# BikeLight.net
KiCad netlist of a schematic drawn in EAGLE
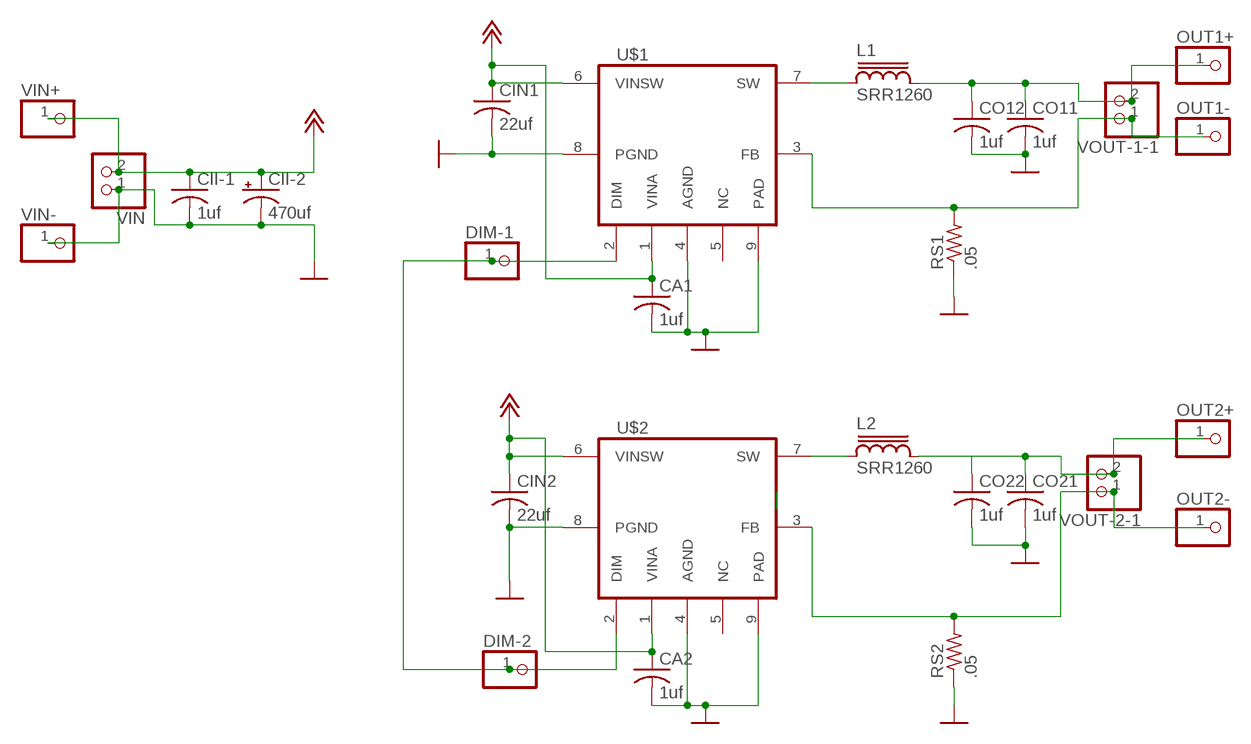
[diagram p0: schematic, sheet 1]

(export (version "E")
  (design (tool "Eeschema 10.0.6"))
  (components
    (comp (ref "CA1")
      (value "1uf")
      (footprint "eagle-import:C1210")
      (libsource (lib "eagle-import") (part "C-USC1210"))
    )
    (comp (ref "CA2")
      (value "1uf")
      (footprint "eagle-import:C1210")
      (libsource (lib "eagle-import") (part "C-USC1210"))
    )
    (comp (ref "CII-1")
      (value "1uf")
      (footprint "eagle-import:C1210")
      (libsource (lib "eagle-import") (part "C-USC1210"))
    )
    (comp (ref "CII-2")
      (value "470uf")
      (footprint "eagle-import:UD-10X10_NICHICON")
      (libsource (lib "eagle-import") (part "CPOL-USUD-10X10"))
    )
    (comp (ref "CIN1")
      (value "22uf")
      (footprint "eagle-import:C1210")
      (libsource (lib "eagle-import") (part "C-USC1210"))
    )
    (comp (ref "CIN2")
      (value "22uf")
      (footprint "eagle-import:C1210")
      (libsource (lib "eagle-import") (part "C-USC1210"))
    )
    (comp (ref "CO11")
      (value "1uf")
      (footprint "eagle-import:C1210")
      (libsource (lib "eagle-import") (part "C-USC1210"))
    )
    (comp (ref "CO12")
      (value "1uf")
      (footprint "eagle-import:C1210")
      (libsource (lib "eagle-import") (part "C-USC1210"))
    )
    (comp (ref "CO21")
      (value "1uf")
      (footprint "eagle-import:C1210")
      (libsource (lib "eagle-import") (part "C-USC1210"))
    )
    (comp (ref "CO22")
      (value "1uf")
      (footprint "eagle-import:C1210")
      (libsource (lib "eagle-import") (part "C-USC1210"))
    )
    (comp (ref "DIM-1")
      (value "PINHD-1X1")
      (footprint "eagle-import:1X01")
      (libsource (lib "eagle-import") (part "PINHD-1X1"))
    )
    (comp (ref "DIM-2")
      (value "PINHD-1X1")
      (footprint "eagle-import:1X01")
      (libsource (lib "eagle-import") (part "PINHD-1X1"))
    )
    (comp (ref "L1")
      (value "SRR1260")
      (footprint "eagle-import:SRR1260")
      (libsource (lib "eagle-import") (part "SRR1260"))
    )
    (comp (ref "L2")
      (value "SRR1260")
      (footprint "eagle-import:SRR1260")
      (libsource (lib "eagle-import") (part "SRR1260"))
    )
    (comp (ref "OUT1+")
      (value "PINHD-1X1")
      (footprint "eagle-import:1X01")
      (libsource (lib "eagle-import") (part "PINHD-1X1"))
    )
    (comp (ref "OUT1-")
      (value "PINHD-1X1")
      (footprint "eagle-import:1X01")
      (libsource (lib "eagle-import") (part "PINHD-1X1"))
    )
    (comp (ref "OUT2+")
      (value "PINHD-1X1")
      (footprint "eagle-import:1X01")
      (libsource (lib "eagle-import") (part "PINHD-1X1"))
    )
    (comp (ref "OUT2-")
      (value "PINHD-1X1")
      (footprint "eagle-import:1X01")
      (libsource (lib "eagle-import") (part "PINHD-1X1"))
    )
    (comp (ref "RS1")
      (value ".05")
      (footprint "eagle-import:R1206")
      (libsource (lib "eagle-import") (part "R-US_R1206"))
    )
    (comp (ref "RS2")
      (value ".05")
      (footprint "eagle-import:R1206")
      (libsource (lib "eagle-import") (part "R-US_R1206"))
    )
    (comp (ref "U$1")
      (value "LED2001PHR")
      (footprint "eagle-import:SOIC127P600X170-9N")
      (libsource (lib "eagle-import") (part "LED2001PHR"))
    )
    (comp (ref "U$2")
      (value "LED2001PHR")
      (footprint "eagle-import:SOIC127P600X170-9N")
      (libsource (lib "eagle-import") (part "LED2001PHR"))
    )
    (comp (ref "VIN")
      (value "PINHD-1X2")
      (footprint "eagle-import:1X02")
      (libsource (lib "eagle-import") (part "PINHD-1X2"))
    )
    (comp (ref "VIN+")
      (value "PINHD-1X1")
      (footprint "eagle-import:1X01")
      (libsource (lib "eagle-import") (part "PINHD-1X1"))
    )
    (comp (ref "VIN-")
      (value "PINHD-1X1")
      (footprint "eagle-import:1X01")
      (libsource (lib "eagle-import") (part "PINHD-1X1"))
    )
    (comp (ref "VOUT-1-1")
      (value "PINHD-1X2")
      (footprint "eagle-import:1X02")
      (libsource (lib "eagle-import") (part "PINHD-1X2"))
    )
    (comp (ref "VOUT-2-1")
      (value "PINHD-1X2")
      (footprint "eagle-import:1X02")
      (libsource (lib "eagle-import") (part "PINHD-1X2"))
    )
  )
  (nets
    (net (code "1") (name "+12V") (class "Default")
      (node (ref "CA1") (pin "1") (pinfunction "1_1") (pintype "passive"))
      (node (ref "CA2") (pin "1") (pinfunction "1_1") (pintype "passive"))
      (node (ref "CII-1") (pin "1") (pinfunction "1_1") (pintype "passive"))
      (node (ref "CII-2") (pin "+") (pinfunction "+_+") (pintype "passive"))
      (node (ref "CIN1") (pin "1") (pinfunction "1_1") (pintype "passive"))
      (node (ref "CIN2") (pin "1") (pinfunction "1_1") (pintype "passive"))
      (node (ref "U$1") (pin "1") (pinfunction "VINA_1") (pintype "input"))
      (node (ref "U$1") (pin "6") (pinfunction "VINSW_6") (pintype "input"))
      (node (ref "U$2") (pin "1") (pinfunction "VINA_1") (pintype "input"))
      (node (ref "U$2") (pin "6") (pinfunction "VINSW_6") (pintype "input"))
      (node (ref "VIN") (pin "2") (pinfunction "2_2") (pintype "passive"))
      (node (ref "VIN+") (pin "1") (pinfunction "1_1") (pintype "passive"))
    )
    (net (code "2") (name "GND") (class "Default")
      (node (ref "CA1") (pin "2") (pinfunction "2_2") (pintype "passive"))
      (node (ref "CA2") (pin "2") (pinfunction "2_2") (pintype "passive"))
      (node (ref "CII-1") (pin "2") (pinfunction "2_2") (pintype "passive"))
      (node (ref "CII-2") (pin "-") (pinfunction "-_-") (pintype "passive"))
      (node (ref "CIN1") (pin "2") (pinfunction "2_2") (pintype "passive"))
      (node (ref "CIN2") (pin "2") (pinfunction "2_2") (pintype "passive"))
      (node (ref "CO11") (pin "2") (pinfunction "2_2") (pintype "passive"))
      (node (ref "CO12") (pin "2") (pinfunction "2_2") (pintype "passive"))
      (node (ref "CO21") (pin "2") (pinfunction "2_2") (pintype "passive"))
      (node (ref "CO22") (pin "2") (pinfunction "2_2") (pintype "passive"))
      (node (ref "RS1") (pin "1") (pinfunction "1_1") (pintype "passive"))
      (node (ref "RS2") (pin "1") (pinfunction "1_1") (pintype "passive"))
      (node (ref "U$1") (pin "4") (pinfunction "AGND_4") (pintype "input"))
      (node (ref "U$1") (pin "8") (pinfunction "PGND_8") (pintype "input"))
      (node (ref "U$1") (pin "9") (pinfunction "PAD_9") (pintype "input"))
      (node (ref "U$2") (pin "4") (pinfunction "AGND_4") (pintype "input"))
      (node (ref "U$2") (pin "8") (pinfunction "PGND_8") (pintype "input"))
      (node (ref "U$2") (pin "9") (pinfunction "PAD_9") (pintype "input"))
      (node (ref "VIN") (pin "1") (pinfunction "1_1") (pintype "passive"))
      (node (ref "VIN-") (pin "1") (pinfunction "1_1") (pintype "passive"))
    )
    (net (code "3") (name "Net-(CO11-Pad1)") (class "Default")
      (node (ref "CO11") (pin "1") (pinfunction "1_1") (pintype "passive"))
      (node (ref "CO12") (pin "1") (pinfunction "1_1") (pintype "passive"))
      (node (ref "L1") (pin "2") (pinfunction "2_2") (pintype "passive"))
      (node (ref "OUT1+") (pin "1") (pinfunction "1_1") (pintype "passive"))
      (node (ref "VOUT-1-1") (pin "2") (pinfunction "2_2") (pintype "passive"))
    )
    (net (code "4") (name "Net-(CO21-Pad1)") (class "Default")
      (node (ref "CO21") (pin "1") (pinfunction "1_1") (pintype "passive"))
      (node (ref "CO22") (pin "1") (pinfunction "1_1") (pintype "passive"))
      (node (ref "L2") (pin "2") (pinfunction "2_2") (pintype "passive"))
      (node (ref "OUT2+") (pin "1") (pinfunction "1_1") (pintype "passive"))
      (node (ref "VOUT-2-1") (pin "2") (pinfunction "2_2") (pintype "passive"))
    )
    (net (code "5") (name "Net-(U$1-DIM)") (class "Default")
      (node (ref "DIM-1") (pin "1") (pinfunction "1_1") (pintype "passive"))
      (node (ref "DIM-2") (pin "1") (pinfunction "1_1") (pintype "passive"))
      (node (ref "U$1") (pin "2") (pinfunction "DIM_2") (pintype "input"))
      (node (ref "U$2") (pin "2") (pinfunction "DIM_2") (pintype "input"))
    )
    (net (code "6") (name "Net-(U$1-FB)") (class "Default")
      (node (ref "OUT1-") (pin "1") (pinfunction "1_1") (pintype "passive"))
      (node (ref "RS1") (pin "2") (pinfunction "2_2") (pintype "passive"))
      (node (ref "U$1") (pin "3") (pinfunction "FB_3") (pintype "input"))
      (node (ref "VOUT-1-1") (pin "1") (pinfunction "1_1") (pintype "passive"))
    )
    (net (code "7") (name "Net-(U$1-SW)") (class "Default")
      (node (ref "L1") (pin "1") (pinfunction "1_1") (pintype "passive"))
      (node (ref "U$1") (pin "7") (pinfunction "SW_7") (pintype "output"))
    )
    (net (code "8") (name "Net-(U$2-FB)") (class "Default")
      (node (ref "OUT2-") (pin "1") (pinfunction "1_1") (pintype "passive"))
      (node (ref "RS2") (pin "2") (pinfunction "2_2") (pintype "passive"))
      (node (ref "U$2") (pin "3") (pinfunction "FB_3") (pintype "input"))
      (node (ref "VOUT-2-1") (pin "1") (pinfunction "1_1") (pintype "passive"))
    )
    (net (code "9") (name "Net-(U$2-SW)") (class "Default")
      (node (ref "L2") (pin "1") (pinfunction "1_1") (pintype "passive"))
      (node (ref "U$2") (pin "7") (pinfunction "SW_7") (pintype "output"))
    )
    (net (code "10") (name "unconnected-(U$1-NC-Pad5)") (class "Default")
      (node (ref "U$1") (pin "5") (pinfunction "NC_5") (pintype "input"))
    )
    (net (code "11") (name "unconnected-(U$2-NC-Pad5)") (class "Default")
      (node (ref "U$2") (pin "5") (pinfunction "NC_5") (pintype "input"))
    )
  )
)
